# Schema.net
KiCad netlist of a schematic drawn in Altium Designer
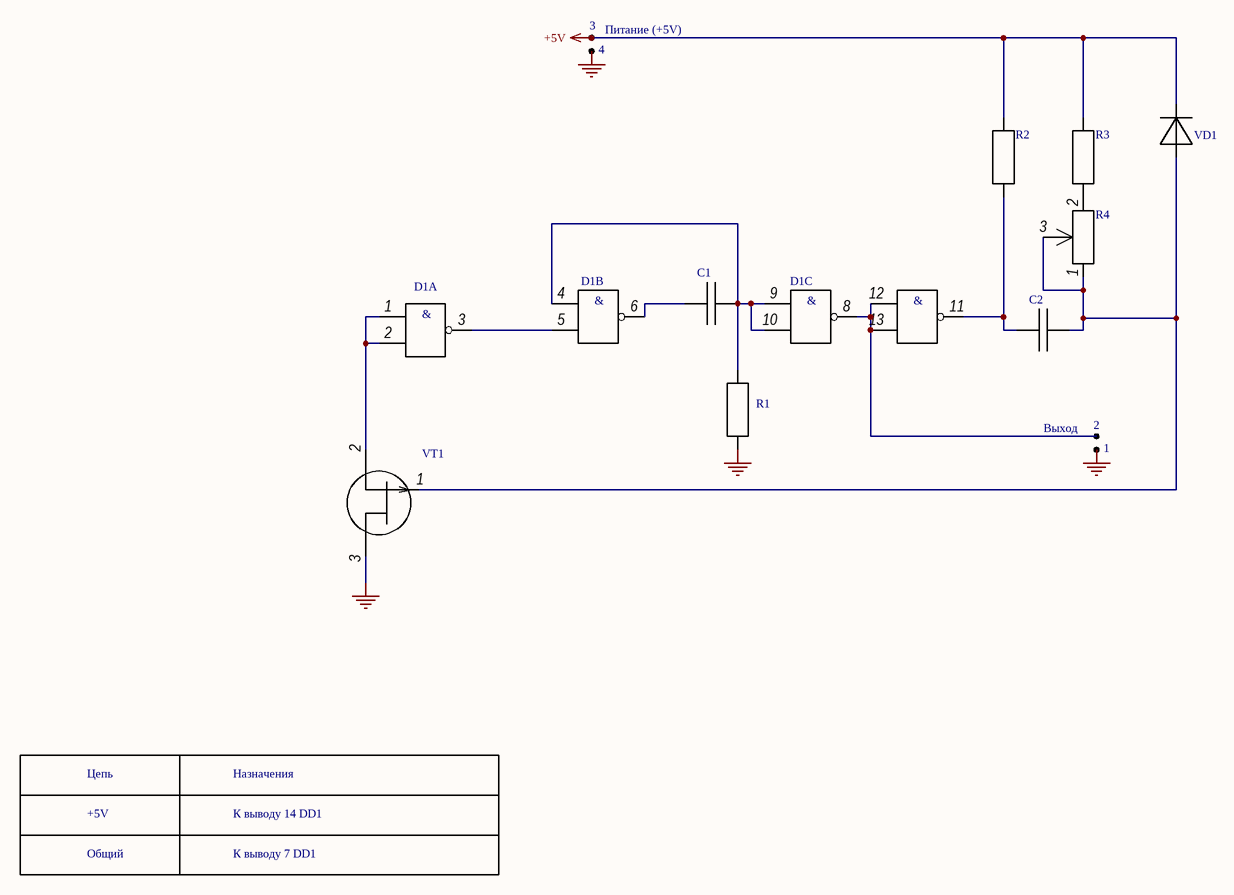
[diagram p0: Schema.SchDoc]

(export (version "E")
  (design (tool "Eeschema 10.0.6"))
  (components
    (comp (ref "1") (value "Point") (footprint "Point") (libsource (lib "Resistor") (part "Point")))
    (comp (ref "2") (value "2") (footprint "Point") (libsource (lib "Resistor") (part "Point")))
    (comp (ref "3") (value "Point") (footprint "Point") (libsource (lib "Resistor") (part "Point")))
    (comp (ref "4") (value "Point") (footprint "Point") (libsource (lib "Resistor") (part "Point")))
    (comp (ref "C1")
      (value "С постоянный")
      (footprint "Capacitors:B37986-N")
      (libsource (lib "Condensators") (part "С постоянный"))
    )
    (comp (ref "C2")
      (value "С постоянный")
      (footprint "Capacitors:B37986-N")
      (libsource (lib "Condensators") (part "С постоянный"))
    )
    (comp (ref "D1")
      (value "~")
      (footprint "Transistor:К155ЛА3")
      (libsource (lib "Integral_Digital") (part "К155ЛА3_ПМ"))
    )
    (comp (ref "R1")
      (value "R_0.125_10")
      (footprint "Resistor:R_ 0,125_10")
      (libsource (lib "Resistor") (part "R_0.125_10"))
    )
    (comp (ref "R2")
      (value "R_0,125_10")
      (footprint "Resistor:R_ 0,125_10")
      (libsource (lib "Resistors") (part "R_0,125_10"))
    )
    (comp (ref "R3")
      (value "R_0,125_10")
      (footprint "Resistor:R_ 0,125_10")
      (libsource (lib "Resistors") (part "R_0,125_10"))
    )
    (comp (ref "R4")
      (value "R регулируемый")
      (footprint "Resistor:R рег_BOURNS3296-3/8")
      (libsource (lib "Resistors") (part "R регулируемый"))
    )
    (comp (ref "VD1") (value "D") (footprint "Extra:D9A") (libsource (lib "Diode") (part "D")))
    (comp (ref "VT1")
      (value "Tранзистор полевой с каналом P-типа")
      (footprint "Transistor:SOT223")
      (libsource (lib "Transistor") (part "Tранзистор полевой с каналом P-типа"))
    )
  )
  (nets
    (net (code "1") (name "+5V") (class "Default")
      (node (ref "3") (pin "1") (pinfunction "1_1") (pintype "passive"))
      (node (ref "D1") (pin "14") (pinfunction "+5V_14") (pintype "power_in"))
      (node (ref "R2") (pin "2") (pinfunction "2_2") (pintype "passive"))
      (node (ref "R3") (pin "2") (pinfunction "2_2") (pintype "passive"))
      (node (ref "VD1") (pin "2") (pinfunction "2_2") (pintype "passive"))
    )
    (net (code "2") (name "/Выход") (class "Default")
      (node (ref "2") (pin "1") (pinfunction "1_1") (pintype "passive"))
      (node (ref "D1") (pin "12") (pinfunction "12_12") (pintype "passive"))
      (node (ref "D1") (pin "13") (pinfunction "13_13") (pintype "passive"))
      (node (ref "D1") (pin "8") (pinfunction "8_8") (pintype "passive"))
    )
    (net (code "3") (name "GND") (class "Default")
      (node (ref "1") (pin "1") (pinfunction "1_1") (pintype "passive"))
      (node (ref "4") (pin "1") (pinfunction "1_1") (pintype "passive"))
      (node (ref "D1") (pin "7") (pinfunction "GND_7") (pintype "power_in"))
      (node (ref "R1") (pin "1") (pinfunction "1_1") (pintype "passive"))
      (node (ref "VT1") (pin "3") (pinfunction "3_3") (pintype "passive"))
    )
    (net (code "4") (name "Net-(C1-Pad1)") (class "Default")
      (node (ref "C1") (pin "1") (pinfunction "1_1") (pintype "passive"))
      (node (ref "D1") (pin "6") (pinfunction "6_6") (pintype "passive"))
    )
    (net (code "5") (name "Net-(C1-Pad2)") (class "Default")
      (node (ref "C1") (pin "2") (pinfunction "2_2") (pintype "passive"))
      (node (ref "D1") (pin "10") (pinfunction "10_10") (pintype "passive"))
      (node (ref "D1") (pin "4") (pinfunction "4_4") (pintype "passive"))
      (node (ref "D1") (pin "9") (pinfunction "9_9") (pintype "passive"))
      (node (ref "R1") (pin "2") (pinfunction "2_2") (pintype "passive"))
    )
    (net (code "6") (name "Net-(C2-Pad1)") (class "Default")
      (node (ref "C2") (pin "1") (pinfunction "1_1") (pintype "passive"))
      (node (ref "D1") (pin "11") (pinfunction "11_11") (pintype "passive"))
      (node (ref "R2") (pin "1") (pinfunction "1_1") (pintype "passive"))
    )
    (net (code "7") (name "Net-(C2-Pad2)") (class "Default")
      (node (ref "C2") (pin "2") (pinfunction "2_2") (pintype "passive"))
      (node (ref "R4") (pin "1") (pinfunction "1_1") (pintype "passive"))
      (node (ref "R4") (pin "3") (pinfunction "3_3") (pintype "passive"))
      (node (ref "VD1") (pin "1") (pinfunction "1_1") (pintype "passive"))
      (node (ref "VT1") (pin "1") (pinfunction "1_1") (pintype "passive"))
    )
    (net (code "8") (name "Net-(D1-Pad1)") (class "Default")
      (node (ref "D1") (pin "1") (pinfunction "1_1") (pintype "passive"))
      (node (ref "D1") (pin "2") (pinfunction "2_2") (pintype "passive"))
      (node (ref "VT1") (pin "2") (pinfunction "2_2") (pintype "passive"))
    )
    (net (code "9") (name "Net-(D1-Pad3)") (class "Default")
      (node (ref "D1") (pin "3") (pinfunction "3_3") (pintype "passive"))
      (node (ref "D1") (pin "5") (pinfunction "5_5") (pintype "passive"))
    )
    (net (code "10") (name "Net-(R3-Pad1)") (class "Default")
      (node (ref "R3") (pin "1") (pinfunction "1_1") (pintype "passive"))
      (node (ref "R4") (pin "2") (pinfunction "2_2") (pintype "passive"))
    )
  )
)
